# Motor-Driver.net
KiCad netlist of a schematic drawn in EAGLE
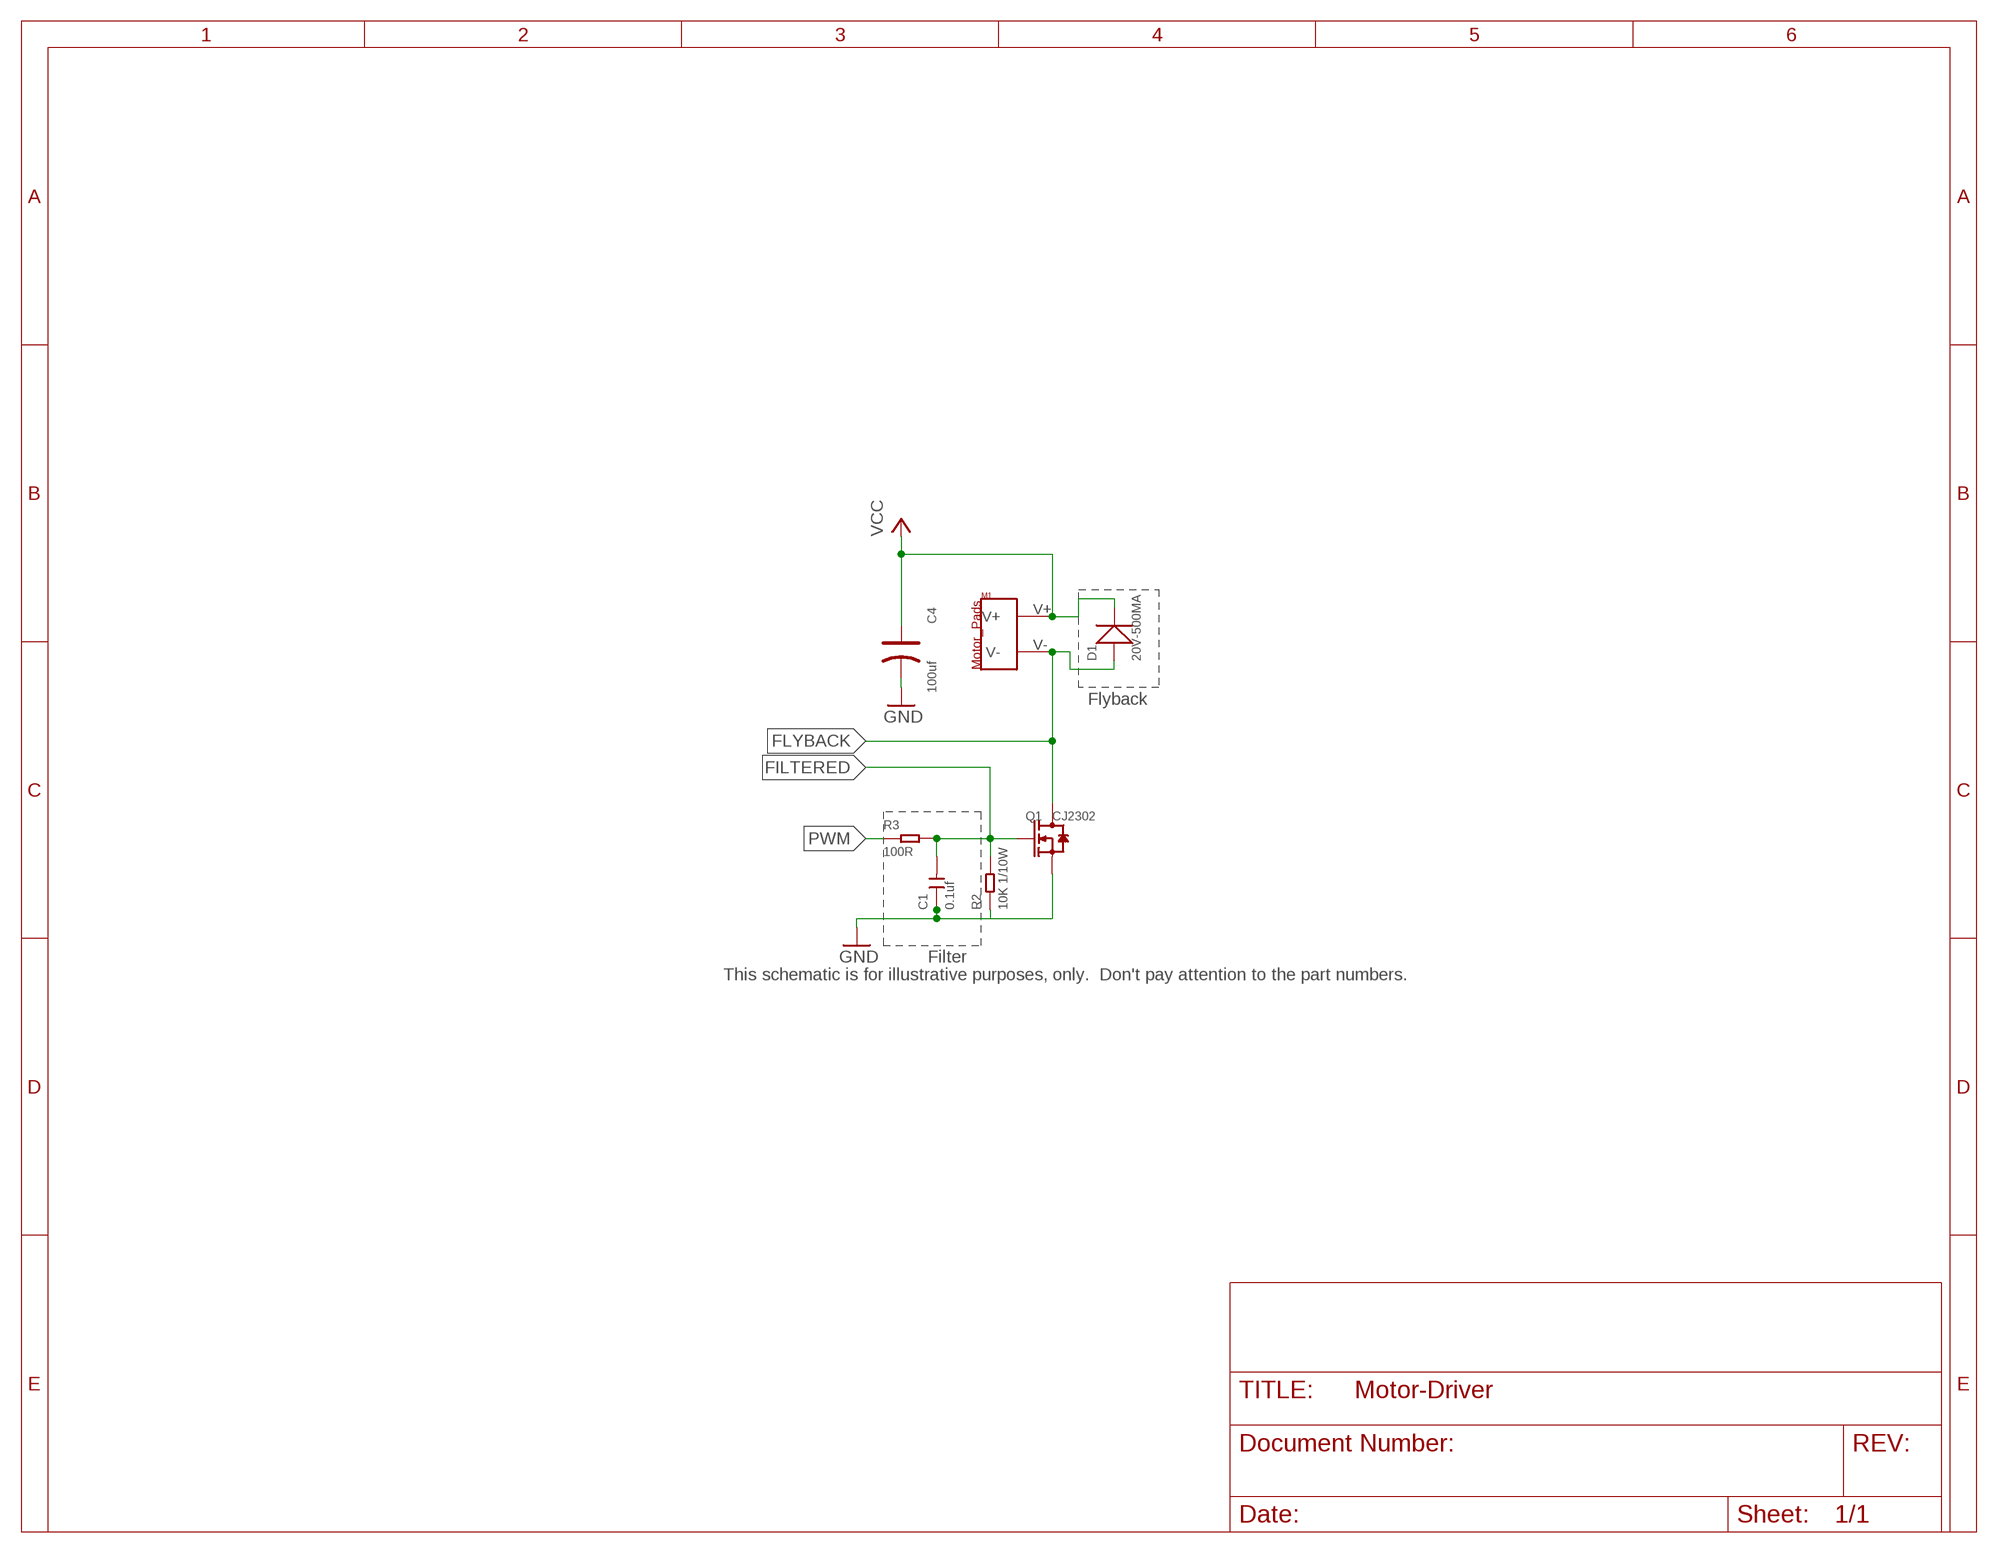
[diagram p0: schematic, sheet 1]

(export (version "E")
  (design (tool "Eeschema 10.0.6"))
  (components
    (comp (ref "C1")
      (value "0.1uf")
      (footprint "eagle-import:C0402")
      (fields (field (name "MPN") "CC0402KRX5R6BB105"))
      (libsource (lib "eagle-import") (part "CERAMIC-1UF-10V-10%-X5R(0402)"))
    )
    (comp (ref "C4")
      (value "100uf")
      (footprint "eagle-import:AVX-B")
      (fields (field (name "MPN") "TAJB107M010#NJ"))
      (libsource (lib "eagle-import") (part "TANTALUM-SMD-100UF-10V(AVX-B)"))
    )
    (comp (ref "D1")
      (value "20V-500MA")
      (footprint "eagle-import:SOD-123")
      (fields (field (name "MPN") "SS0520-7-F"))
      (libsource (lib "eagle-import") (part "SMD-DIODE-SCHOTTKY-20V-500MA(SOD-123)"))
    )
    (comp (ref "M1")
      (value "MOTOR_PADS")
      (footprint "eagle-import:MOTOR_PADS")
      (libsource (lib "eagle-import") (part "MOTOR_PADS"))
    )
    (comp (ref "Q1")
      (value "CJ2302")
      (footprint "eagle-import:SOT-23")
      (libsource (lib "eagle-import") (part "SMD-MOSFET-N-CH-20V-2.1A-CJ2302(SOT-23)"))
    )
    (comp (ref "R2")
      (value "10K 1/10W")
      (footprint "eagle-import:R0603")
      (fields (field (name "MPN") "RC0603JR-0710KL"))
      (libsource (lib "eagle-import") (part "SMD-RES-10K-5%-1/10W(0603)"))
    )
    (comp (ref "R3")
      (value "100R")
      (footprint "eagle-import:R0603")
      (fields (field (name "MPN") "RC0603JR-07100RL"))
      (libsource (lib "eagle-import") (part "SMD-RES-100R-5%-1/10W(0603)"))
    )
  )
  (nets
    (net (code "1") (name "FILTERED") (class "Default")
      (node (ref "C1") (pin "2") (pinfunction "2_2") (pintype "passive"))
      (node (ref "Q1") (pin "1") (pinfunction "G_1") (pintype "passive"))
      (node (ref "R2") (pin "2") (pinfunction "2_2") (pintype "passive"))
      (node (ref "R3") (pin "2") (pinfunction "2_2") (pintype "passive"))
    )
    (net (code "2") (name "FLYBACK") (class "Default")
      (node (ref "D1") (pin "+") (pinfunction "+_+") (pintype "passive"))
      (node (ref "M1") (pin "V-") (pinfunction "V-_V-") (pintype "bidirectional"))
      (node (ref "Q1") (pin "3") (pinfunction "D_3") (pintype "passive"))
    )
    (net (code "3") (name "GND") (class "Default")
      (node (ref "C1") (pin "1") (pinfunction "1_1") (pintype "passive"))
      (node (ref "C4") (pin "-") (pinfunction "-_-") (pintype "passive"))
      (node (ref "Q1") (pin "2") (pinfunction "S_2") (pintype "passive"))
      (node (ref "R2") (pin "1") (pinfunction "1_1") (pintype "passive"))
    )
    (net (code "4") (name "PWM") (class "Default")
      (node (ref "R3") (pin "1") (pinfunction "1_1") (pintype "passive"))
    )
    (net (code "5") (name "VCC") (class "Default")
      (node (ref "C4") (pin "+") (pinfunction "+_+") (pintype "passive"))
      (node (ref "D1") (pin "-") (pinfunction "-_-") (pintype "passive"))
      (node (ref "M1") (pin "V+") (pinfunction "V+_V+") (pintype "bidirectional"))
    )
  )
)
